# Audio_Bord.net
KiCad netlist of a schematic drawn in EAGLE
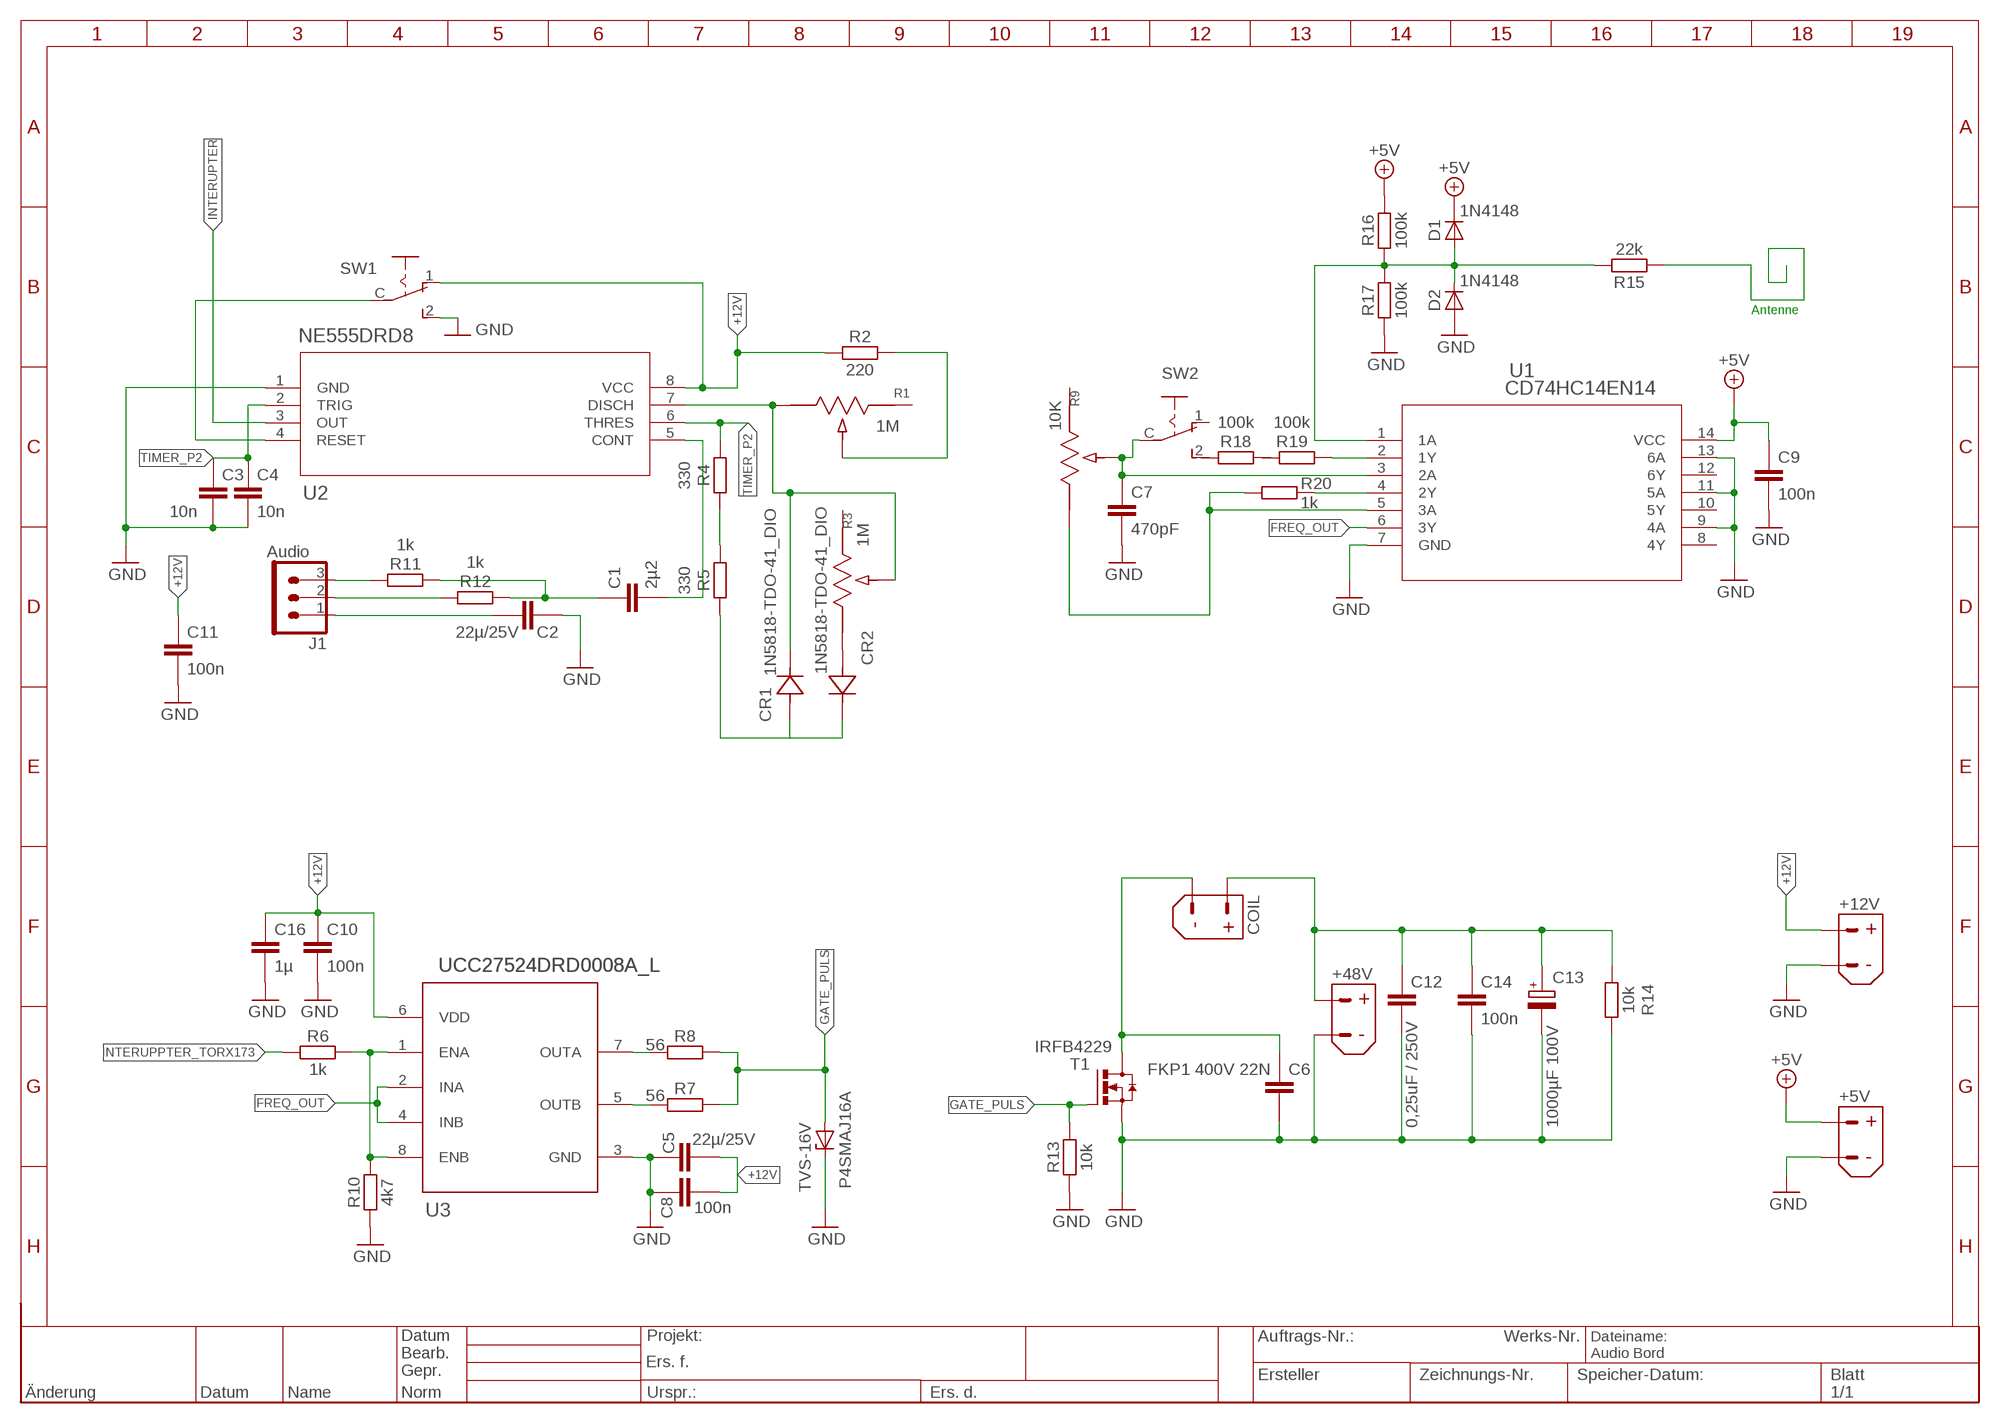
[diagram p0: schematic, sheet 1]

(export (version "E")
  (design (tool "Eeschema 10.0.6"))
  (components
    (comp (ref "+5V")
      (value "XT60UPB-M")
      (footprint "eagle-import:XT60UPB-M")
      (libsource (lib "eagle-import") (part "XT60?-MUPB"))
    )
    (comp (ref "+12V")
      (value "XT60UPB-M")
      (footprint "eagle-import:XT60UPB-M")
      (libsource (lib "eagle-import") (part "XT60?-MUPB"))
    )
    (comp (ref "+48V")
      (value "XT60UPB-M")
      (footprint "eagle-import:XT60UPB-M")
      (libsource (lib "eagle-import") (part "XT60?-MUPB"))
    )
    (comp (ref "C1")
      (value "2µ2")
      (footprint "eagle-import:C1206")
      (libsource (lib "eagle-import") (part "C-EU_-?C12062U2"))
    )
    (comp (ref "C2")
      (value "22µ/25V")
      (footprint "eagle-import:C1206")
      (libsource (lib "eagle-import") (part "C-EU_-?C120622U-25V"))
    )
    (comp (ref "C3")
      (value "10n")
      (footprint "eagle-import:C0603")
      (libsource (lib "eagle-import") (part "C-EU_-?C060310N"))
    )
    (comp (ref "C4")
      (value "10n")
      (footprint "eagle-import:C0603")
      (libsource (lib "eagle-import") (part "C-EU_-?C060310N"))
    )
    (comp (ref "C5")
      (value "22µ/25V")
      (footprint "eagle-import:C1206")
      (libsource (lib "eagle-import") (part "C-EU_-?C120622U-25V"))
    )
    (comp (ref "C6")
      (value "FKP1 400V 22N")
      (footprint "eagle-import:C1206")
      (libsource (lib "eagle-import") (part "C-EU_C1206"))
    )
    (comp (ref "C7")
      (value "470pF")
      (footprint "eagle-import:C1206")
      (libsource (lib "eagle-import") (part "C-EU_C1206"))
    )
    (comp (ref "C8")
      (value "100n")
      (footprint "eagle-import:C1206")
      (libsource (lib "eagle-import") (part "C-EU_-?C1206100N"))
    )
    (comp (ref "C9")
      (value "100n")
      (footprint "eagle-import:C1206")
      (libsource (lib "eagle-import") (part "C-EU_-?C1206100N"))
    )
    (comp (ref "C10")
      (value "100n")
      (footprint "eagle-import:C1206")
      (libsource (lib "eagle-import") (part "C-EU_-?C1206100N"))
    )
    (comp (ref "C11")
      (value "100n")
      (footprint "eagle-import:C1206")
      (libsource (lib "eagle-import") (part "C-EU_-?C1206100N"))
    )
    (comp (ref "C12")
      (value "0,25uF / 250V")
      (footprint "eagle-import:C1206")
      (libsource (lib "eagle-import") (part "C-EU_C1206"))
    )
    (comp (ref "C13")
      (value "1000µF 100V")
      (footprint "eagle-import:E2-5")
      (libsource (lib "eagle-import") (part "CPOL-EU_E2-5"))
    )
    (comp (ref "C14")
      (value "100n")
      (footprint "eagle-import:C1206")
      (libsource (lib "eagle-import") (part "C-EU_-?C1206100N"))
    )
    (comp (ref "C16")
      (value "1µ")
      (footprint "eagle-import:C1206")
      (libsource (lib "eagle-import") (part "C-EU_-?C12061U"))
    )
    (comp (ref "COIL")
      (value "XT60UPB-M")
      (footprint "eagle-import:XT60UPB-M")
      (libsource (lib "eagle-import") (part "XT60?-MUPB"))
    )
    (comp (ref "CR1")
      (value "1N5818-TDO-41_DIO")
      (footprint "eagle-import:DO-41_DIO")
      (fields
        (field (name "MANUFACTURER_PART_NUMBER") "1N5818-T")
        (field (name "COPYRIGHT") "Copyright (C) 2026 Ultra Librarian. All rights reserved.")
      )
      (libsource (lib "eagle-import") (part "1N5818-TDO-41_DIO"))
    )
    (comp (ref "CR2")
      (value "1N5818-TDO-41_DIO")
      (footprint "eagle-import:DO-41_DIO")
      (fields
        (field (name "MANUFACTURER_PART_NUMBER") "1N5818-T")
        (field (name "COPYRIGHT") "Copyright (C) 2026 Ultra Librarian. All rights reserved.")
      )
      (libsource (lib "eagle-import") (part "1N5818-TDO-41_DIO"))
    )
    (comp (ref "D1")
      (value "1N4148")
      (footprint "eagle-import:SOD523")
      (libsource (lib "eagle-import") (part "DIODE--?SOD5231N4148"))
    )
    (comp (ref "D2")
      (value "1N4148")
      (footprint "eagle-import:SOD523")
      (libsource (lib "eagle-import") (part "DIODE--?SOD5231N4148"))
    )
    (comp (ref "J1")
      (value "Audio")
      (footprint "eagle-import:PSS-03G")
      (libsource (lib "eagle-import") (part "PSS-1X3G"))
    )
    (comp (ref "P4SMAJ16A")
      (value "TVS-16V")
      (footprint "eagle-import:DO214AC_SMA")
      (libsource (lib "eagle-import") (part "Z-DIODE--?DO214ACTSV-16V"))
    )
    (comp (ref "R1")
      (value "1M")
      (footprint "eagle-import:POT_3296X")
      (fields
        (field (name "MANUFACTURER_PART_NUMBER") "3296X-1-102LF")
        (field (name "COPYRIGHT") "Copyright (C) 2026 Ultra Librarian. All rights reserved.")
      )
      (libsource (lib "eagle-import") (part "3296X-1-102LFPOT_3296X"))
    )
    (comp (ref "R2")
      (value "220")
      (footprint "eagle-import:R1206")
      (libsource (lib "eagle-import") (part "R-EU_-?R1206220"))
    )
    (comp (ref "R3")
      (value "1M")
      (footprint "eagle-import:POT_3296X")
      (fields
        (field (name "MANUFACTURER_PART_NUMBER") "3296X-1-102LF")
        (field (name "COPYRIGHT") "Copyright (C) 2026 Ultra Librarian. All rights reserved.")
      )
      (libsource (lib "eagle-import") (part "3296X-1-102LFPOT_3296X"))
    )
    (comp (ref "R4")
      (value "330")
      (footprint "eagle-import:R0805")
      (libsource (lib "eagle-import") (part "R-EU_-?R0805330"))
    )
    (comp (ref "R5")
      (value "330")
      (footprint "eagle-import:R0805")
      (libsource (lib "eagle-import") (part "R-EU_-?R0805330"))
    )
    (comp (ref "R6")
      (value "1k")
      (footprint "eagle-import:R1206")
      (libsource (lib "eagle-import") (part "R-EU_-?R12061K"))
    )
    (comp (ref "R7")
      (value "56")
      (footprint "eagle-import:R1206")
      (libsource (lib "eagle-import") (part "R-EU_-?R120656"))
    )
    (comp (ref "R8")
      (value "56")
      (footprint "eagle-import:R1206")
      (libsource (lib "eagle-import") (part "R-EU_-?R120656"))
    )
    (comp (ref "R9")
      (value "10K")
      (footprint "eagle-import:POT_3296X")
      (fields
        (field (name "MANUFACTURER_PART_NUMBER") "3296X-1-102LF")
        (field (name "COPYRIGHT") "Copyright (C) 2026 Ultra Librarian. All rights reserved.")
      )
      (libsource (lib "eagle-import") (part "3296X-1-102LFPOT_3296X"))
    )
    (comp (ref "R10")
      (value "4k7")
      (footprint "eagle-import:R1206")
      (libsource (lib "eagle-import") (part "R-EU_-?R12064K7"))
    )
    (comp (ref "R11")
      (value "1k")
      (footprint "eagle-import:R1206")
      (libsource (lib "eagle-import") (part "R-EU_-?R12061K"))
    )
    (comp (ref "R12")
      (value "1k")
      (footprint "eagle-import:R1206")
      (libsource (lib "eagle-import") (part "R-EU_-?R12061K"))
    )
    (comp (ref "R13")
      (value "10k")
      (footprint "eagle-import:R1206")
      (libsource (lib "eagle-import") (part "R-EU_-?R120610K"))
    )
    (comp (ref "R14")
      (value "10k")
      (footprint "eagle-import:R1206")
      (libsource (lib "eagle-import") (part "R-EU_-?R120610K"))
    )
    (comp (ref "R15")
      (value "22k")
      (footprint "eagle-import:R1206")
      (libsource (lib "eagle-import") (part "R-EU_-?R120622K"))
    )
    (comp (ref "R16")
      (value "100k")
      (footprint "eagle-import:R1206")
      (libsource (lib "eagle-import") (part "R-EU_-?R1206100K"))
    )
    (comp (ref "R17")
      (value "100k")
      (footprint "eagle-import:R1206")
      (libsource (lib "eagle-import") (part "R-EU_-?R1206100K"))
    )
    (comp (ref "R18")
      (value "100k")
      (footprint "eagle-import:R1206")
      (libsource (lib "eagle-import") (part "R-EU_-?R1206100K"))
    )
    (comp (ref "R19")
      (value "100k")
      (footprint "eagle-import:R1206")
      (libsource (lib "eagle-import") (part "R-EU_-?R1206100K"))
    )
    (comp (ref "R20")
      (value "1k")
      (footprint "eagle-import:R1206")
      (libsource (lib "eagle-import") (part "R-EU_-?R12061K"))
    )
    (comp (ref "SW1")
      (value "SW_SPDT_ESP10")
      (footprint "eagle-import:ESP10XX")
      (libsource (lib "eagle-import") (part "SW_SPDT_ESP10"))
    )
    (comp (ref "SW2")
      (value "SW_SPDT_ESP10")
      (footprint "eagle-import:ESP10XX")
      (libsource (lib "eagle-import") (part "SW_SPDT_ESP10"))
    )
    (comp (ref "T1")
      (value "IRFB4229")
      (footprint "eagle-import:PG-TO263-3")
      (libsource (lib "eagle-import") (part "IPB020N10N5"))
    )
    (comp (ref "U1")
      (value "CD74HC14EN14")
      (footprint "eagle-import:N14")
      (fields
        (field (name "MANUFACTURER_PART_NUMBER") "CD74HC14E")
        (field (name "COPYRIGHT") "Copyright (C) 2026 Ultra Librarian. All rights reserved.")
      )
      (libsource (lib "eagle-import") (part "CD74HC14EN14"))
    )
    (comp (ref "U2")
      (value "NE555DRD8")
      (footprint "eagle-import:D8")
      (fields
        (field (name "MANUFACTURER_PART_NUMBER") "NE555DR")
        (field (name "COPYRIGHT") "Copyright (C) 2026 Ultra Librarian. All rights reserved.")
      )
      (libsource (lib "eagle-import") (part "NE555DRD8"))
    )
    (comp (ref "U3")
      (value "UCC27524DRD0008A_L")
      (footprint "eagle-import:D0008A_L")
      (fields
        (field (name "MANUFACTURER_PART_NUMBER") "UCC27524DR")
        (field (name "COPYRIGHT") "Copyright (C) 2026 Ultra Librarian. All rights reserved.")
      )
      (libsource (lib "eagle-import") (part "UCC27524DRD0008A_L"))
    )
  )
  (nets
    (net (code "1") (name "+5V") (class "Default")
      (node (ref "+5V") (pin "+") (pinfunction "+_+") (pintype "passive"))
      (node (ref "C9") (pin "1") (pinfunction "1_1") (pintype "passive"))
      (node (ref "D1") (pin "C") (pinfunction "C_C") (pintype "passive"))
      (node (ref "R16") (pin "2") (pinfunction "2_2") (pintype "passive"))
      (node (ref "U1") (pin "14") (pinfunction "VCC_14") (pintype "power_in"))
    )
    (net (code "2") (name "+12V") (class "Default")
      (node (ref "+12V") (pin "+") (pinfunction "+_+") (pintype "passive"))
      (node (ref "C10") (pin "1") (pinfunction "1_1") (pintype "passive"))
      (node (ref "C11") (pin "1") (pinfunction "1_1") (pintype "passive"))
      (node (ref "C16") (pin "1") (pinfunction "1_1") (pintype "passive"))
      (node (ref "C5") (pin "2") (pinfunction "2_2") (pintype "passive"))
      (node (ref "C8") (pin "2") (pinfunction "2_2") (pintype "passive"))
      (node (ref "R2") (pin "1") (pinfunction "1_1") (pintype "passive"))
      (node (ref "SW1") (pin "1") (pinfunction "NC_1") (pintype "passive"))
      (node (ref "U2") (pin "8") (pinfunction "VCC_8") (pintype "power_in"))
      (node (ref "U3") (pin "6") (pinfunction "VDD_6") (pintype "power_in"))
    )
    (net (code "3") (name "FREQ_OUT") (class "Default")
      (node (ref "U1") (pin "6") (pinfunction "3Y_6") (pintype "output"))
      (node (ref "U3") (pin "2") (pinfunction "INA_2") (pintype "input"))
      (node (ref "U3") (pin "4") (pinfunction "INB_4") (pintype "input"))
    )
    (net (code "4") (name "GATE_PULS") (class "Default")
      (node (ref "P4SMAJ16A") (pin "A") (pinfunction "A_A") (pintype "passive"))
      (node (ref "R13") (pin "2") (pinfunction "2_2") (pintype "passive"))
      (node (ref "R7") (pin "2") (pinfunction "2_2") (pintype "passive"))
      (node (ref "R8") (pin "2") (pinfunction "2_2") (pintype "passive"))
      (node (ref "T1") (pin "1") (pinfunction "G_1") (pintype "passive"))
    )
    (net (code "5") (name "GND") (class "Default")
      (node (ref "+12V") (pin "-") (pinfunction "-_-") (pintype "passive"))
      (node (ref "+48V") (pin "-") (pinfunction "-_-") (pintype "passive"))
      (node (ref "+5V") (pin "-") (pinfunction "-_-") (pintype "passive"))
      (node (ref "C10") (pin "2") (pinfunction "2_2") (pintype "passive"))
      (node (ref "C11") (pin "2") (pinfunction "2_2") (pintype "passive"))
      (node (ref "C12") (pin "2") (pinfunction "2_2") (pintype "passive"))
      (node (ref "C13") (pin "-") (pinfunction "-_-") (pintype "passive"))
      (node (ref "C14") (pin "2") (pinfunction "2_2") (pintype "passive"))
      (node (ref "C16") (pin "2") (pinfunction "2_2") (pintype "passive"))
      (node (ref "C2") (pin "2") (pinfunction "2_2") (pintype "passive"))
      (node (ref "C3") (pin "2") (pinfunction "2_2") (pintype "passive"))
      (node (ref "C4") (pin "2") (pinfunction "2_2") (pintype "passive"))
      (node (ref "C5") (pin "1") (pinfunction "1_1") (pintype "passive"))
      (node (ref "C6") (pin "2") (pinfunction "2_2") (pintype "passive"))
      (node (ref "C7") (pin "2") (pinfunction "2_2") (pintype "passive"))
      (node (ref "C8") (pin "1") (pinfunction "1_1") (pintype "passive"))
      (node (ref "C9") (pin "2") (pinfunction "2_2") (pintype "passive"))
      (node (ref "D2") (pin "A") (pinfunction "A_A") (pintype "passive"))
      (node (ref "P4SMAJ16A") (pin "C") (pinfunction "C_C") (pintype "passive"))
      (node (ref "R10") (pin "1") (pinfunction "1_1") (pintype "passive"))
      (node (ref "R13") (pin "1") (pinfunction "1_1") (pintype "passive"))
      (node (ref "R14") (pin "1") (pinfunction "1_1") (pintype "passive"))
      (node (ref "R17") (pin "1") (pinfunction "1_1") (pintype "passive"))
      (node (ref "SW1") (pin "2") (pinfunction "NO_2") (pintype "passive"))
      (node (ref "T1") (pin "3") (pinfunction "S_3") (pintype "passive"))
      (node (ref "U1") (pin "11") (pinfunction "5A_11") (pintype "input"))
      (node (ref "U1") (pin "13") (pinfunction "6A_13") (pintype "input"))
      (node (ref "U1") (pin "7") (pinfunction "GND_7") (pintype "power_in"))
      (node (ref "U1") (pin "9") (pinfunction "4A_9") (pintype "input"))
      (node (ref "U2") (pin "1") (pinfunction "GND_1") (pintype "power_in"))
      (node (ref "U3") (pin "3") (pinfunction "GND_3") (pintype "power_in"))
    )
    (net (code "6") (name "INTERUPPTER_TORX173") (class "Default")
      (node (ref "R6") (pin "1") (pinfunction "1_1") (pintype "passive"))
    )
    (net (code "7") (name "INTERUPTER") (class "Default")
      (node (ref "U2") (pin "3") (pinfunction "OUT_3") (pintype "output"))
    )
    (net (code "8") (name "Net-(+48V-Pad+)") (class "Default")
      (node (ref "+48V") (pin "+") (pinfunction "+_+") (pintype "passive"))
      (node (ref "C12") (pin "1") (pinfunction "1_1") (pintype "passive"))
      (node (ref "C13") (pin "+") (pinfunction "+_+") (pintype "passive"))
      (node (ref "C14") (pin "1") (pinfunction "1_1") (pintype "passive"))
      (node (ref "COIL") (pin "+") (pinfunction "+_+") (pintype "passive"))
      (node (ref "R14") (pin "2") (pinfunction "2_2") (pintype "passive"))
    )
    (net (code "9") (name "Net-(C1-Pad1)") (class "Default")
      (node (ref "C1") (pin "1") (pinfunction "1_1") (pintype "passive"))
      (node (ref "R11") (pin "2") (pinfunction "2_2") (pintype "passive"))
      (node (ref "R12") (pin "2") (pinfunction "2_2") (pintype "passive"))
    )
    (net (code "10") (name "Net-(C2-Pad1)") (class "Default")
      (node (ref "C2") (pin "1") (pinfunction "1_1") (pintype "passive"))
      (node (ref "J1") (pin "1") (pinfunction "1_1") (pintype "passive"))
    )
    (net (code "11") (name "Net-(CR1-Pad2)") (class "Default")
      (node (ref "CR1") (pin "2") (pinfunction "2_2") (pintype "passive"))
      (node (ref "CR2") (pin "1") (pinfunction "1_1") (pintype "passive"))
      (node (ref "R5") (pin "1") (pinfunction "1_1") (pintype "passive"))
    )
    (net (code "12") (name "Net-(CR2-Pad2)") (class "Default")
      (node (ref "CR2") (pin "2") (pinfunction "2_2") (pintype "passive"))
      (node (ref "R3") (pin "3") (pinfunction "3_3") (pintype "passive"))
    )
    (net (code "13") (name "Net-(J1-Pad2)") (class "Default")
      (node (ref "J1") (pin "2") (pinfunction "2_2") (pintype "passive"))
      (node (ref "R12") (pin "1") (pinfunction "1_1") (pintype "passive"))
    )
    (net (code "14") (name "Net-(J1-Pad3)") (class "Default")
      (node (ref "J1") (pin "3") (pinfunction "3_3") (pintype "passive"))
      (node (ref "R11") (pin "1") (pinfunction "1_1") (pintype "passive"))
    )
    (net (code "15") (name "Net-(R1-Pad2)") (class "Default")
      (node (ref "R1") (pin "2") (pinfunction "2_2") (pintype "passive"))
      (node (ref "R2") (pin "2") (pinfunction "2_2") (pintype "passive"))
    )
    (net (code "16") (name "Net-(R4-Pad1)") (class "Default")
      (node (ref "R4") (pin "1") (pinfunction "1_1") (pintype "passive"))
      (node (ref "R5") (pin "2") (pinfunction "2_2") (pintype "passive"))
    )
    (net (code "17") (name "Net-(T1-D)") (class "Default")
      (node (ref "C6") (pin "1") (pinfunction "1_1") (pintype "passive"))
      (node (ref "COIL") (pin "-") (pinfunction "-_-") (pintype "passive"))
      (node (ref "T1") (pin "4") (pinfunction "D_4") (pintype "passive"))
    )
    (net (code "18") (name "Net-(U1-1A)") (class "Default")
      (node (ref "D1") (pin "A") (pinfunction "A_A") (pintype "passive"))
      (node (ref "D2") (pin "C") (pinfunction "C_C") (pintype "passive"))
      (node (ref "R15") (pin "2") (pinfunction "2_2") (pintype "passive"))
      (node (ref "R16") (pin "1") (pinfunction "1_1") (pintype "passive"))
      (node (ref "R17") (pin "2") (pinfunction "2_2") (pintype "passive"))
      (node (ref "U1") (pin "1") (pinfunction "1A_1") (pintype "input"))
    )
    (net (code "19") (name "Net-(U1-1Y)") (class "Default")
      (node (ref "R19") (pin "2") (pinfunction "2_2") (pintype "passive"))
      (node (ref "U1") (pin "2") (pinfunction "1Y_2") (pintype "output"))
    )
    (net (code "20") (name "Net-(U1-2A)") (class "Default")
      (node (ref "C7") (pin "1") (pinfunction "1_1") (pintype "passive"))
      (node (ref "R9") (pin "2") (pinfunction "2_2") (pintype "passive"))
      (node (ref "SW2") (pin "C") (pinfunction "C_C") (pintype "passive"))
      (node (ref "U1") (pin "3") (pinfunction "2A_3") (pintype "input"))
    )
    (net (code "21") (name "Net-(U1-2Y)") (class "Default")
      (node (ref "R20") (pin "2") (pinfunction "2_2") (pintype "passive"))
      (node (ref "U1") (pin "4") (pinfunction "2Y_4") (pintype "output"))
    )
    (net (code "22") (name "Net-(U1-3A)") (class "Default")
      (node (ref "R20") (pin "1") (pinfunction "1_1") (pintype "passive"))
      (node (ref "R9") (pin "3") (pinfunction "3_3") (pintype "passive"))
      (node (ref "U1") (pin "5") (pinfunction "3A_5") (pintype "input"))
    )
    (net (code "23") (name "Net-(U2-CONT)") (class "Default")
      (node (ref "C1") (pin "2") (pinfunction "2_2") (pintype "passive"))
      (node (ref "U2") (pin "5") (pinfunction "CONT_5") (pintype "passive"))
    )
    (net (code "24") (name "Net-(U2-DISCH)") (class "Default")
      (node (ref "CR1") (pin "1") (pinfunction "1_1") (pintype "passive"))
      (node (ref "R1") (pin "3") (pinfunction "3_3") (pintype "passive"))
      (node (ref "R3") (pin "2") (pinfunction "2_2") (pintype "passive"))
      (node (ref "U2") (pin "7") (pinfunction "DISCH_7") (pintype "passive"))
    )
    (net (code "25") (name "Net-(U2-RESET)") (class "Default")
      (node (ref "SW1") (pin "C") (pinfunction "C_C") (pintype "passive"))
      (node (ref "U2") (pin "4") (pinfunction "RESET_4") (pintype "input"))
    )
    (net (code "26") (name "Net-(U3-ENA)") (class "Default")
      (node (ref "R10") (pin "2") (pinfunction "2_2") (pintype "passive"))
      (node (ref "R6") (pin "2") (pinfunction "2_2") (pintype "passive"))
      (node (ref "U3") (pin "1") (pinfunction "ENA_1") (pintype "input"))
      (node (ref "U3") (pin "8") (pinfunction "ENB_8") (pintype "input"))
    )
    (net (code "27") (name "Net-(U3-OUTA)") (class "Default")
      (node (ref "R8") (pin "1") (pinfunction "1_1") (pintype "passive"))
      (node (ref "U3") (pin "7") (pinfunction "OUTA_7") (pintype "output"))
    )
    (net (code "28") (name "Net-(U3-OUTB)") (class "Default")
      (node (ref "R7") (pin "1") (pinfunction "1_1") (pintype "passive"))
      (node (ref "U3") (pin "5") (pinfunction "OUTB_5") (pintype "output"))
    )
    (net (code "29") (name "TIMER_P2") (class "Default")
      (node (ref "C3") (pin "1") (pinfunction "1_1") (pintype "passive"))
      (node (ref "C4") (pin "1") (pinfunction "1_1") (pintype "passive"))
      (node (ref "R4") (pin "2") (pinfunction "2_2") (pintype "passive"))
      (node (ref "U2") (pin "2") (pinfunction "TRIG_2") (pintype "input"))
      (node (ref "U2") (pin "6") (pinfunction "THRES_6") (pintype "input"))
    )
    (net (code "30") (name "unconnected-(R1-Pad1)") (class "Default")
      (node (ref "R1") (pin "1") (pinfunction "1_1") (pintype "passive"))
    )
    (net (code "31") (name "unconnected-(R3-Pad1)") (class "Default")
      (node (ref "R3") (pin "1") (pinfunction "1_1") (pintype "passive"))
    )
    (net (code "32") (name "unconnected-(R9-Pad1)") (class "Default")
      (node (ref "R9") (pin "1") (pinfunction "1_1") (pintype "passive"))
    )
    (net (code "33") (name "unconnected-(R15-Pad1)") (class "Default")
      (node (ref "R15") (pin "1") (pinfunction "1_1") (pintype "passive"))
    )
    (net (code "34") (name "unconnected-(R18-Pad1)") (class "Default")
      (node (ref "R18") (pin "1") (pinfunction "1_1") (pintype "passive"))
    )
    (net (code "35") (name "unconnected-(R18-Pad2)") (class "Default")
      (node (ref "R18") (pin "2") (pinfunction "2_2") (pintype "passive"))
    )
    (net (code "36") (name "unconnected-(R19-Pad1)") (class "Default")
      (node (ref "R19") (pin "1") (pinfunction "1_1") (pintype "passive"))
    )
    (net (code "37") (name "unconnected-(SW2-NC-Pad1)") (class "Default")
      (node (ref "SW2") (pin "1") (pinfunction "NC_1") (pintype "passive"))
    )
    (net (code "38") (name "unconnected-(SW2-NO-Pad2)") (class "Default")
      (node (ref "SW2") (pin "2") (pinfunction "NO_2") (pintype "passive"))
    )
    (net (code "39") (name "unconnected-(U1-4Y-Pad8)") (class "Default")
      (node (ref "U1") (pin "8") (pinfunction "4Y_8") (pintype "output"))
    )
    (net (code "40") (name "unconnected-(U1-5Y-Pad10)") (class "Default")
      (node (ref "U1") (pin "10") (pinfunction "5Y_10") (pintype "output"))
    )
    (net (code "41") (name "unconnected-(U1-6Y-Pad12)") (class "Default")
      (node (ref "U1") (pin "12") (pinfunction "6Y_12") (pintype "output"))
    )
  )
)
